# Own_FeatherWing_Doubler_1X2_v1_0_Final_A.net
KiCad netlist of a schematic drawn in EAGLE
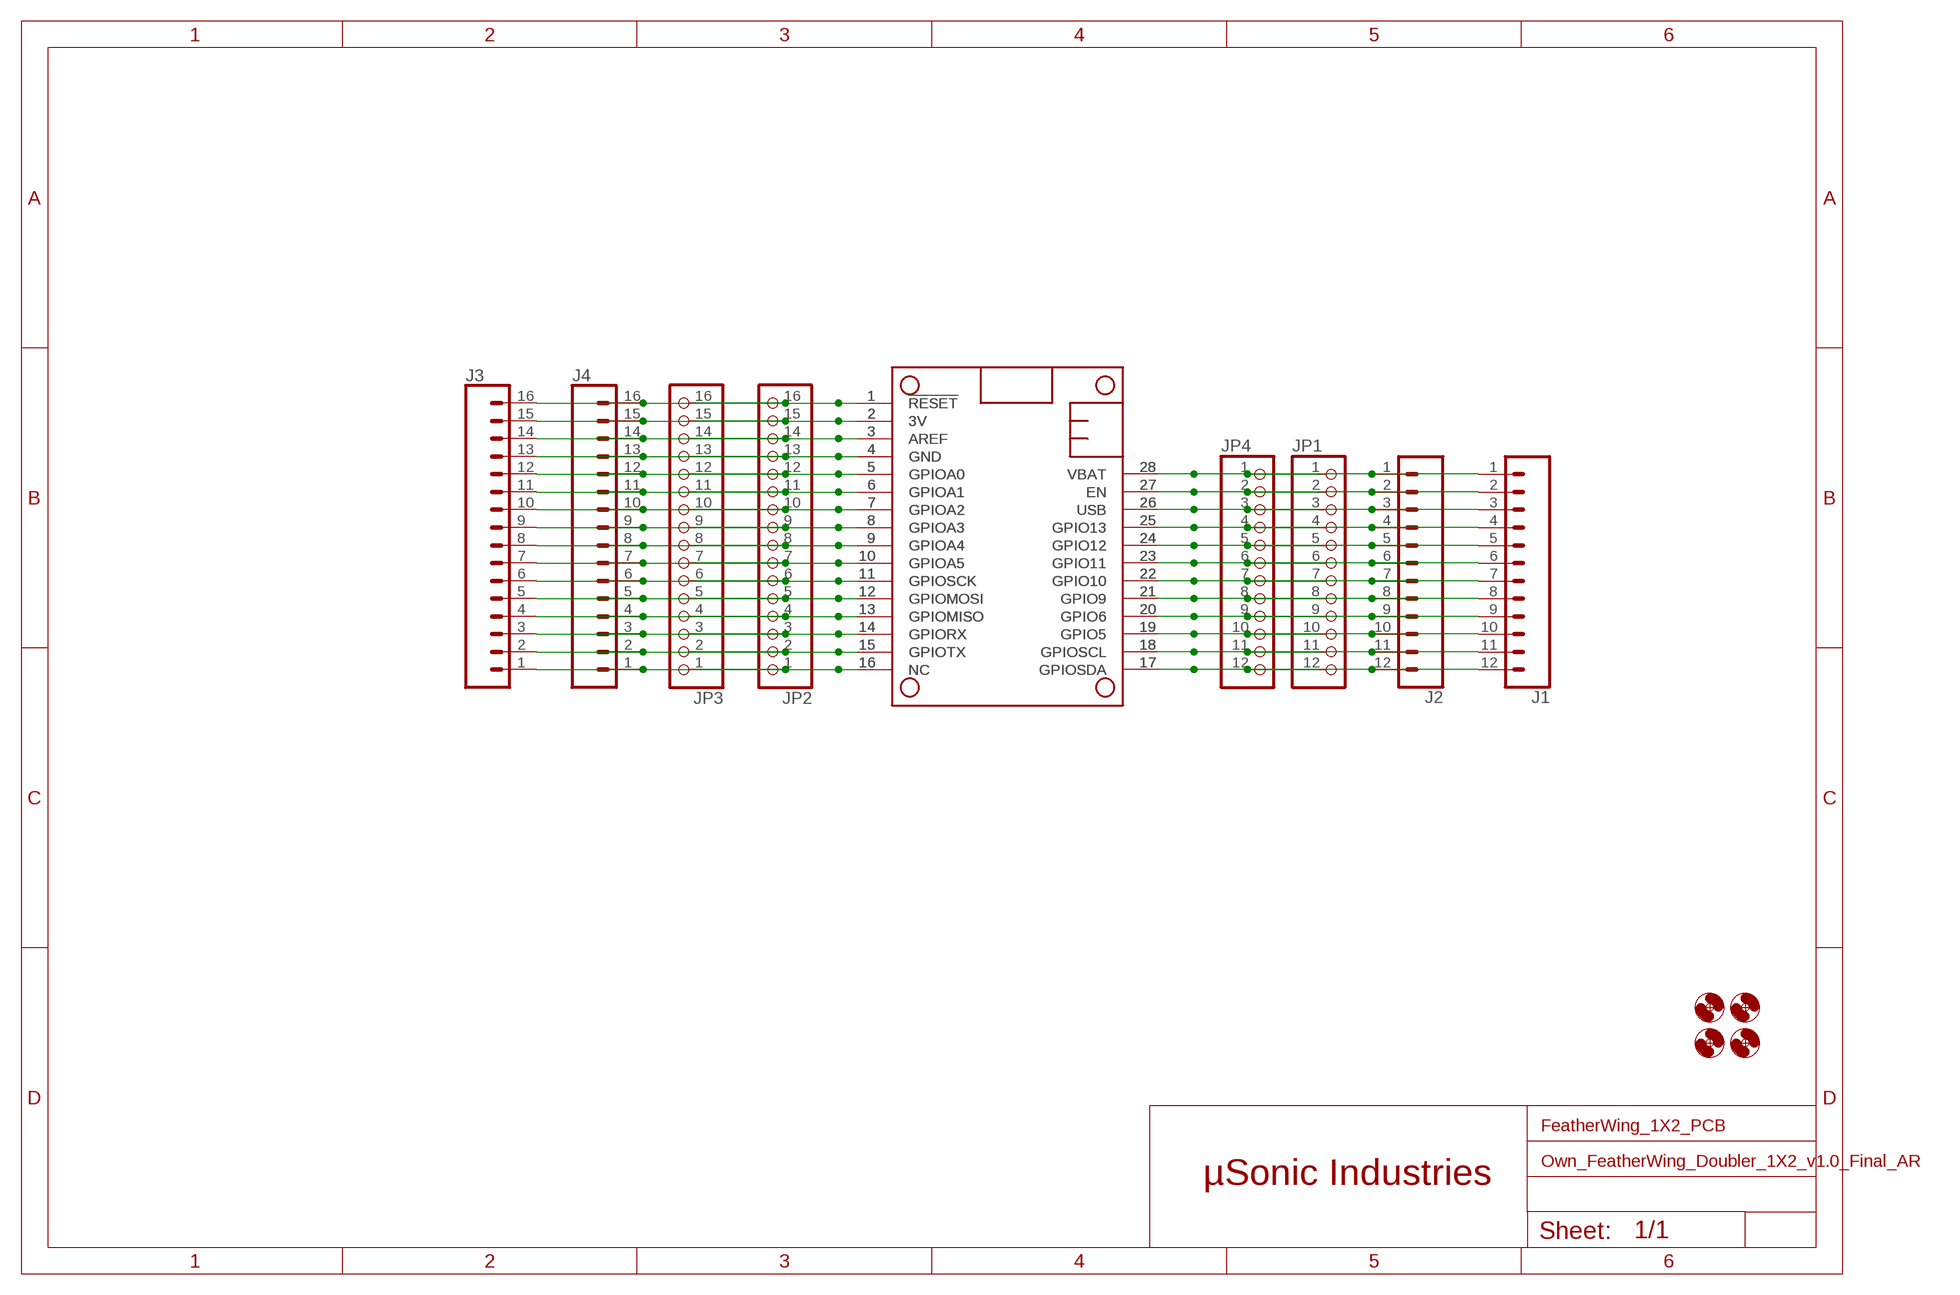
[diagram p0: schematic, sheet 1]

(export (version "E")
  (design (tool "Eeschema 10.0.6"))
  (components
    (comp (ref "J1")
      (value "CONN_12NO_SILK")
      (footprint "eagle-import:1X12_NO_SILK")
      (libsource (lib "eagle-import") (part "CONN_12NO_SILK"))
    )
    (comp (ref "J2")
      (value "CONN_12NO_SILK")
      (footprint "eagle-import:1X12_NO_SILK")
      (libsource (lib "eagle-import") (part "CONN_12NO_SILK"))
    )
    (comp (ref "J3")
      (value "CONN_161X16_NO_SILK")
      (footprint "eagle-import:1X16_NO_SILK")
      (libsource (lib "eagle-import") (part "CONN_161X16_NO_SILK"))
    )
    (comp (ref "J4")
      (value "CONN_161X16_NO_SILK")
      (footprint "eagle-import:1X16_NO_SILK")
      (libsource (lib "eagle-import") (part "CONN_161X16_NO_SILK"))
    )
    (comp (ref "JP1")
      (value "HEADER-1X1276MIL")
      (footprint "eagle-import:1X12_ROUND_76MIL")
      (libsource (lib "eagle-import") (part "HEADER-1X1276MIL"))
    )
    (comp (ref "JP2")
      (value "HEADER-1X16_76MIL")
      (footprint "eagle-import:1X16_ROUND_76MIL")
      (libsource (lib "eagle-import") (part "HEADER-1X16_76MIL"))
    )
    (comp (ref "JP3")
      (value "HEADER-1X16_76MIL")
      (footprint "eagle-import:1X16_ROUND_76MIL")
      (libsource (lib "eagle-import") (part "HEADER-1X16_76MIL"))
    )
    (comp (ref "JP4")
      (value "HEADER-1X1276MIL")
      (footprint "eagle-import:1X12_ROUND_76MIL")
      (libsource (lib "eagle-import") (part "HEADER-1X1276MIL"))
    )
    (comp (ref "MS1")
      (value "FEATHERWING_NODIM")
      (footprint "eagle-import:FEATHERWING_DIM")
      (libsource (lib "eagle-import") (part "FEATHERWING_NODIM"))
    )
    (comp (ref "MS2")
      (value "FEATHERWING_NODIM")
      (footprint "eagle-import:FEATHERWING_DIM")
      (libsource (lib "eagle-import") (part "FEATHERWING_NODIM"))
    )
    (comp (ref "U$2")
      (value "MOUNTHOLEBIG")
      (footprint "eagle-import:OWN_MOUNTHOLE_BIGAREA")
      (libsource (lib "eagle-import") (part "MOUNTHOLEBIG"))
    )
    (comp (ref "U$3")
      (value "MOUNTHOLEBIG")
      (footprint "eagle-import:OWN_MOUNTHOLE_BIGAREA")
      (libsource (lib "eagle-import") (part "MOUNTHOLEBIG"))
    )
    (comp (ref "U$4")
      (value "MOUNTHOLEBIG")
      (footprint "eagle-import:OWN_MOUNTHOLE_BIGAREA")
      (libsource (lib "eagle-import") (part "MOUNTHOLEBIG"))
    )
    (comp (ref "U$5")
      (value "MOUNTHOLEBIG")
      (footprint "eagle-import:OWN_MOUNTHOLE_BIGAREA")
      (libsource (lib "eagle-import") (part "MOUNTHOLEBIG"))
    )
  )
  (nets
    (net (code "1") (name "Net-(MS1-3V)") (class "Default")
      (node (ref "J3") (pin "15") (pinfunction "15_15") (pintype "passive"))
      (node (ref "J4") (pin "15") (pinfunction "15_15") (pintype "passive"))
      (node (ref "JP2") (pin "15") (pinfunction "15_15") (pintype "passive"))
      (node (ref "JP3") (pin "15") (pinfunction "15_15") (pintype "passive"))
      (node (ref "MS1") (pin "2") (pinfunction "3V_2") (pintype "power_in"))
      (node (ref "MS2") (pin "2") (pinfunction "3V_2") (pintype "power_in"))
    )
    (net (code "2") (name "Net-(MS1-AREF)") (class "Default")
      (node (ref "J3") (pin "14") (pinfunction "14_14") (pintype "passive"))
      (node (ref "J4") (pin "14") (pinfunction "14_14") (pintype "passive"))
      (node (ref "JP2") (pin "14") (pinfunction "14_14") (pintype "passive"))
      (node (ref "JP3") (pin "14") (pinfunction "14_14") (pintype "passive"))
      (node (ref "MS1") (pin "3") (pinfunction "AREF_3") (pintype "passive"))
      (node (ref "MS2") (pin "3") (pinfunction "AREF_3") (pintype "passive"))
    )
    (net (code "3") (name "Net-(MS1-EN)") (class "Default")
      (node (ref "J1") (pin "2") (pinfunction "2_2") (pintype "passive"))
      (node (ref "J2") (pin "2") (pinfunction "2_2") (pintype "passive"))
      (node (ref "JP1") (pin "2") (pinfunction "2_2") (pintype "passive"))
      (node (ref "JP4") (pin "2") (pinfunction "2_2") (pintype "passive"))
      (node (ref "MS1") (pin "27") (pinfunction "EN_27") (pintype "passive"))
      (node (ref "MS2") (pin "27") (pinfunction "EN_27") (pintype "passive"))
    )
    (net (code "4") (name "Net-(MS1-GND)") (class "Default")
      (node (ref "J3") (pin "13") (pinfunction "13_13") (pintype "passive"))
      (node (ref "J4") (pin "13") (pinfunction "13_13") (pintype "passive"))
      (node (ref "JP2") (pin "13") (pinfunction "13_13") (pintype "passive"))
      (node (ref "JP3") (pin "13") (pinfunction "13_13") (pintype "passive"))
      (node (ref "MS1") (pin "4") (pinfunction "GND_4") (pintype "power_in"))
      (node (ref "MS2") (pin "4") (pinfunction "GND_4") (pintype "power_in"))
    )
    (net (code "5") (name "Net-(MS1-GPIO5)") (class "Default")
      (node (ref "J1") (pin "10") (pinfunction "10_10") (pintype "passive"))
      (node (ref "J2") (pin "10") (pinfunction "10_10") (pintype "passive"))
      (node (ref "JP1") (pin "10") (pinfunction "10_10") (pintype "passive"))
      (node (ref "JP4") (pin "10") (pinfunction "10_10") (pintype "passive"))
      (node (ref "MS1") (pin "19") (pinfunction "GPIO5_19") (pintype "bidirectional"))
      (node (ref "MS2") (pin "19") (pinfunction "GPIO5_19") (pintype "bidirectional"))
    )
    (net (code "6") (name "Net-(MS1-GPIO6)") (class "Default")
      (node (ref "J1") (pin "9") (pinfunction "9_9") (pintype "passive"))
      (node (ref "J2") (pin "9") (pinfunction "9_9") (pintype "passive"))
      (node (ref "JP1") (pin "9") (pinfunction "9_9") (pintype "passive"))
      (node (ref "JP4") (pin "9") (pinfunction "9_9") (pintype "passive"))
      (node (ref "MS1") (pin "20") (pinfunction "GPIO6_20") (pintype "bidirectional"))
      (node (ref "MS2") (pin "20") (pinfunction "GPIO6_20") (pintype "bidirectional"))
    )
    (net (code "7") (name "Net-(MS1-GPIO9)") (class "Default")
      (node (ref "J1") (pin "8") (pinfunction "8_8") (pintype "passive"))
      (node (ref "J2") (pin "8") (pinfunction "8_8") (pintype "passive"))
      (node (ref "JP1") (pin "8") (pinfunction "8_8") (pintype "passive"))
      (node (ref "JP4") (pin "8") (pinfunction "8_8") (pintype "passive"))
      (node (ref "MS1") (pin "21") (pinfunction "GPIO9_21") (pintype "bidirectional"))
      (node (ref "MS2") (pin "21") (pinfunction "GPIO9_21") (pintype "bidirectional"))
    )
    (net (code "8") (name "Net-(MS1-GPIO10)") (class "Default")
      (node (ref "J1") (pin "7") (pinfunction "7_7") (pintype "passive"))
      (node (ref "J2") (pin "7") (pinfunction "7_7") (pintype "passive"))
      (node (ref "JP1") (pin "7") (pinfunction "7_7") (pintype "passive"))
      (node (ref "JP4") (pin "7") (pinfunction "7_7") (pintype "passive"))
      (node (ref "MS1") (pin "22") (pinfunction "GPIO10_22") (pintype "bidirectional"))
      (node (ref "MS2") (pin "22") (pinfunction "GPIO10_22") (pintype "bidirectional"))
    )
    (net (code "9") (name "Net-(MS1-GPIO11)") (class "Default")
      (node (ref "J1") (pin "6") (pinfunction "6_6") (pintype "passive"))
      (node (ref "J2") (pin "6") (pinfunction "6_6") (pintype "passive"))
      (node (ref "JP1") (pin "6") (pinfunction "6_6") (pintype "passive"))
      (node (ref "JP4") (pin "6") (pinfunction "6_6") (pintype "passive"))
      (node (ref "MS1") (pin "23") (pinfunction "GPIO11_23") (pintype "bidirectional"))
      (node (ref "MS2") (pin "23") (pinfunction "GPIO11_23") (pintype "bidirectional"))
    )
    (net (code "10") (name "Net-(MS1-GPIO12)") (class "Default")
      (node (ref "J1") (pin "5") (pinfunction "5_5") (pintype "passive"))
      (node (ref "J2") (pin "5") (pinfunction "5_5") (pintype "passive"))
      (node (ref "JP1") (pin "5") (pinfunction "5_5") (pintype "passive"))
      (node (ref "JP4") (pin "5") (pinfunction "5_5") (pintype "passive"))
      (node (ref "MS1") (pin "24") (pinfunction "GPIO12_24") (pintype "bidirectional"))
      (node (ref "MS2") (pin "24") (pinfunction "GPIO12_24") (pintype "bidirectional"))
    )
    (net (code "11") (name "Net-(MS1-GPIO13)") (class "Default")
      (node (ref "J1") (pin "4") (pinfunction "4_4") (pintype "passive"))
      (node (ref "J2") (pin "4") (pinfunction "4_4") (pintype "passive"))
      (node (ref "JP1") (pin "4") (pinfunction "4_4") (pintype "passive"))
      (node (ref "JP4") (pin "4") (pinfunction "4_4") (pintype "passive"))
      (node (ref "MS1") (pin "25") (pinfunction "GPIO13_25") (pintype "bidirectional"))
      (node (ref "MS2") (pin "25") (pinfunction "GPIO13_25") (pintype "bidirectional"))
    )
    (net (code "12") (name "Net-(MS1-GPIOA0)") (class "Default")
      (node (ref "J3") (pin "12") (pinfunction "12_12") (pintype "passive"))
      (node (ref "J4") (pin "12") (pinfunction "12_12") (pintype "passive"))
      (node (ref "JP2") (pin "12") (pinfunction "12_12") (pintype "passive"))
      (node (ref "JP3") (pin "12") (pinfunction "12_12") (pintype "passive"))
      (node (ref "MS1") (pin "5") (pinfunction "GPIOA0_5") (pintype "bidirectional"))
      (node (ref "MS2") (pin "5") (pinfunction "GPIOA0_5") (pintype "bidirectional"))
    )
    (net (code "13") (name "Net-(MS1-GPIOA1)") (class "Default")
      (node (ref "J3") (pin "11") (pinfunction "11_11") (pintype "passive"))
      (node (ref "J4") (pin "11") (pinfunction "11_11") (pintype "passive"))
      (node (ref "JP2") (pin "11") (pinfunction "11_11") (pintype "passive"))
      (node (ref "JP3") (pin "11") (pinfunction "11_11") (pintype "passive"))
      (node (ref "MS1") (pin "6") (pinfunction "GPIOA1_6") (pintype "bidirectional"))
      (node (ref "MS2") (pin "6") (pinfunction "GPIOA1_6") (pintype "bidirectional"))
    )
    (net (code "14") (name "Net-(MS1-GPIOA2)") (class "Default")
      (node (ref "J3") (pin "10") (pinfunction "10_10") (pintype "passive"))
      (node (ref "J4") (pin "10") (pinfunction "10_10") (pintype "passive"))
      (node (ref "JP2") (pin "10") (pinfunction "10_10") (pintype "passive"))
      (node (ref "JP3") (pin "10") (pinfunction "10_10") (pintype "passive"))
      (node (ref "MS1") (pin "7") (pinfunction "GPIOA2_7") (pintype "bidirectional"))
      (node (ref "MS2") (pin "7") (pinfunction "GPIOA2_7") (pintype "bidirectional"))
    )
    (net (code "15") (name "Net-(MS1-GPIOA3)") (class "Default")
      (node (ref "J3") (pin "9") (pinfunction "9_9") (pintype "passive"))
      (node (ref "J4") (pin "9") (pinfunction "9_9") (pintype "passive"))
      (node (ref "JP2") (pin "9") (pinfunction "9_9") (pintype "passive"))
      (node (ref "JP3") (pin "9") (pinfunction "9_9") (pintype "passive"))
      (node (ref "MS1") (pin "8") (pinfunction "GPIOA3_8") (pintype "bidirectional"))
      (node (ref "MS2") (pin "8") (pinfunction "GPIOA3_8") (pintype "bidirectional"))
    )
    (net (code "16") (name "Net-(MS1-GPIOA4)") (class "Default")
      (node (ref "J3") (pin "8") (pinfunction "8_8") (pintype "passive"))
      (node (ref "J4") (pin "8") (pinfunction "8_8") (pintype "passive"))
      (node (ref "JP2") (pin "8") (pinfunction "8_8") (pintype "passive"))
      (node (ref "JP3") (pin "8") (pinfunction "8_8") (pintype "passive"))
      (node (ref "MS1") (pin "9") (pinfunction "GPIOA4_9") (pintype "bidirectional"))
      (node (ref "MS2") (pin "9") (pinfunction "GPIOA4_9") (pintype "bidirectional"))
    )
    (net (code "17") (name "Net-(MS1-GPIOA5)") (class "Default")
      (node (ref "J3") (pin "7") (pinfunction "7_7") (pintype "passive"))
      (node (ref "J4") (pin "7") (pinfunction "7_7") (pintype "passive"))
      (node (ref "JP2") (pin "7") (pinfunction "7_7") (pintype "passive"))
      (node (ref "JP3") (pin "7") (pinfunction "7_7") (pintype "passive"))
      (node (ref "MS1") (pin "10") (pinfunction "GPIOA5_10") (pintype "bidirectional"))
      (node (ref "MS2") (pin "10") (pinfunction "GPIOA5_10") (pintype "bidirectional"))
    )
    (net (code "18") (name "Net-(MS1-GPIOMISO)") (class "Default")
      (node (ref "J3") (pin "4") (pinfunction "4_4") (pintype "passive"))
      (node (ref "J4") (pin "4") (pinfunction "4_4") (pintype "passive"))
      (node (ref "JP2") (pin "4") (pinfunction "4_4") (pintype "passive"))
      (node (ref "JP3") (pin "4") (pinfunction "4_4") (pintype "passive"))
      (node (ref "MS1") (pin "13") (pinfunction "GPIOMISO_13") (pintype "bidirectional"))
      (node (ref "MS2") (pin "13") (pinfunction "GPIOMISO_13") (pintype "bidirectional"))
    )
    (net (code "19") (name "Net-(MS1-GPIOMOSI)") (class "Default")
      (node (ref "J3") (pin "5") (pinfunction "5_5") (pintype "passive"))
      (node (ref "J4") (pin "5") (pinfunction "5_5") (pintype "passive"))
      (node (ref "JP2") (pin "5") (pinfunction "5_5") (pintype "passive"))
      (node (ref "JP3") (pin "5") (pinfunction "5_5") (pintype "passive"))
      (node (ref "MS1") (pin "12") (pinfunction "GPIOMOSI_12") (pintype "bidirectional"))
      (node (ref "MS2") (pin "12") (pinfunction "GPIOMOSI_12") (pintype "bidirectional"))
    )
    (net (code "20") (name "Net-(MS1-GPIORX)") (class "Default")
      (node (ref "J3") (pin "3") (pinfunction "3_3") (pintype "passive"))
      (node (ref "J4") (pin "3") (pinfunction "3_3") (pintype "passive"))
      (node (ref "JP2") (pin "3") (pinfunction "3_3") (pintype "passive"))
      (node (ref "JP3") (pin "3") (pinfunction "3_3") (pintype "passive"))
      (node (ref "MS1") (pin "14") (pinfunction "GPIORX_14") (pintype "bidirectional"))
      (node (ref "MS2") (pin "14") (pinfunction "GPIORX_14") (pintype "bidirectional"))
    )
    (net (code "21") (name "Net-(MS1-GPIOSCK)") (class "Default")
      (node (ref "J3") (pin "6") (pinfunction "6_6") (pintype "passive"))
      (node (ref "J4") (pin "6") (pinfunction "6_6") (pintype "passive"))
      (node (ref "JP2") (pin "6") (pinfunction "6_6") (pintype "passive"))
      (node (ref "JP3") (pin "6") (pinfunction "6_6") (pintype "passive"))
      (node (ref "MS1") (pin "11") (pinfunction "GPIOSCK_11") (pintype "bidirectional"))
      (node (ref "MS2") (pin "11") (pinfunction "GPIOSCK_11") (pintype "bidirectional"))
    )
    (net (code "22") (name "Net-(MS1-GPIOSCL)") (class "Default")
      (node (ref "J1") (pin "11") (pinfunction "11_11") (pintype "passive"))
      (node (ref "J2") (pin "11") (pinfunction "11_11") (pintype "passive"))
      (node (ref "JP1") (pin "11") (pinfunction "11_11") (pintype "passive"))
      (node (ref "JP4") (pin "11") (pinfunction "11_11") (pintype "passive"))
      (node (ref "MS1") (pin "18") (pinfunction "GPIOSCL_18") (pintype "bidirectional"))
      (node (ref "MS2") (pin "18") (pinfunction "GPIOSCL_18") (pintype "bidirectional"))
    )
    (net (code "23") (name "Net-(MS1-GPIOSDA)") (class "Default")
      (node (ref "J1") (pin "12") (pinfunction "12_12") (pintype "passive"))
      (node (ref "J2") (pin "12") (pinfunction "12_12") (pintype "passive"))
      (node (ref "JP1") (pin "12") (pinfunction "12_12") (pintype "passive"))
      (node (ref "JP4") (pin "12") (pinfunction "12_12") (pintype "passive"))
      (node (ref "MS1") (pin "17") (pinfunction "GPIOSDA_17") (pintype "bidirectional"))
      (node (ref "MS2") (pin "17") (pinfunction "GPIOSDA_17") (pintype "bidirectional"))
    )
    (net (code "24") (name "Net-(MS1-GPIOTX)") (class "Default")
      (node (ref "J3") (pin "2") (pinfunction "2_2") (pintype "passive"))
      (node (ref "J4") (pin "2") (pinfunction "2_2") (pintype "passive"))
      (node (ref "JP2") (pin "2") (pinfunction "2_2") (pintype "passive"))
      (node (ref "JP3") (pin "2") (pinfunction "2_2") (pintype "passive"))
      (node (ref "MS1") (pin "15") (pinfunction "GPIOTX_15") (pintype "bidirectional"))
      (node (ref "MS2") (pin "15") (pinfunction "GPIOTX_15") (pintype "bidirectional"))
    )
    (net (code "25") (name "Net-(MS1-NC)") (class "Default")
      (node (ref "J3") (pin "1") (pinfunction "1_1") (pintype "passive"))
      (node (ref "J4") (pin "1") (pinfunction "1_1") (pintype "passive"))
      (node (ref "JP2") (pin "1") (pinfunction "1_1") (pintype "passive"))
      (node (ref "JP3") (pin "1") (pinfunction "1_1") (pintype "passive"))
      (node (ref "MS1") (pin "16") (pinfunction "NC_16") (pintype "passive"))
      (node (ref "MS2") (pin "16") (pinfunction "NC_16") (pintype "passive"))
    )
    (net (code "26") (name "Net-(MS1-USB)") (class "Default")
      (node (ref "J1") (pin "3") (pinfunction "3_3") (pintype "passive"))
      (node (ref "J2") (pin "3") (pinfunction "3_3") (pintype "passive"))
      (node (ref "JP1") (pin "3") (pinfunction "3_3") (pintype "passive"))
      (node (ref "JP4") (pin "3") (pinfunction "3_3") (pintype "passive"))
      (node (ref "MS1") (pin "26") (pinfunction "USB_26") (pintype "power_in"))
      (node (ref "MS2") (pin "26") (pinfunction "USB_26") (pintype "power_in"))
    )
    (net (code "27") (name "Net-(MS1-VBAT)") (class "Default")
      (node (ref "J1") (pin "1") (pinfunction "1_1") (pintype "passive"))
      (node (ref "J2") (pin "1") (pinfunction "1_1") (pintype "passive"))
      (node (ref "JP1") (pin "1") (pinfunction "1_1") (pintype "passive"))
      (node (ref "JP4") (pin "1") (pinfunction "1_1") (pintype "passive"))
      (node (ref "MS1") (pin "28") (pinfunction "VBAT_28") (pintype "power_in"))
      (node (ref "MS2") (pin "28") (pinfunction "VBAT_28") (pintype "power_in"))
    )
    (net (code "28") (name "Net-(MS1-~{RESET})") (class "Default")
      (node (ref "J3") (pin "16") (pinfunction "16_16") (pintype "passive"))
      (node (ref "J4") (pin "16") (pinfunction "16_16") (pintype "passive"))
      (node (ref "JP2") (pin "16") (pinfunction "16_16") (pintype "passive"))
      (node (ref "JP3") (pin "16") (pinfunction "16_16") (pintype "passive"))
      (node (ref "MS1") (pin "1") (pinfunction "~{RESET}_1") (pintype "input"))
      (node (ref "MS2") (pin "1") (pinfunction "~{RESET}_1") (pintype "input"))
    )
  )
)
